# Mini_ELRS_2_4GHz_TX.net
KiCad netlist of a schematic drawn in EAGLE
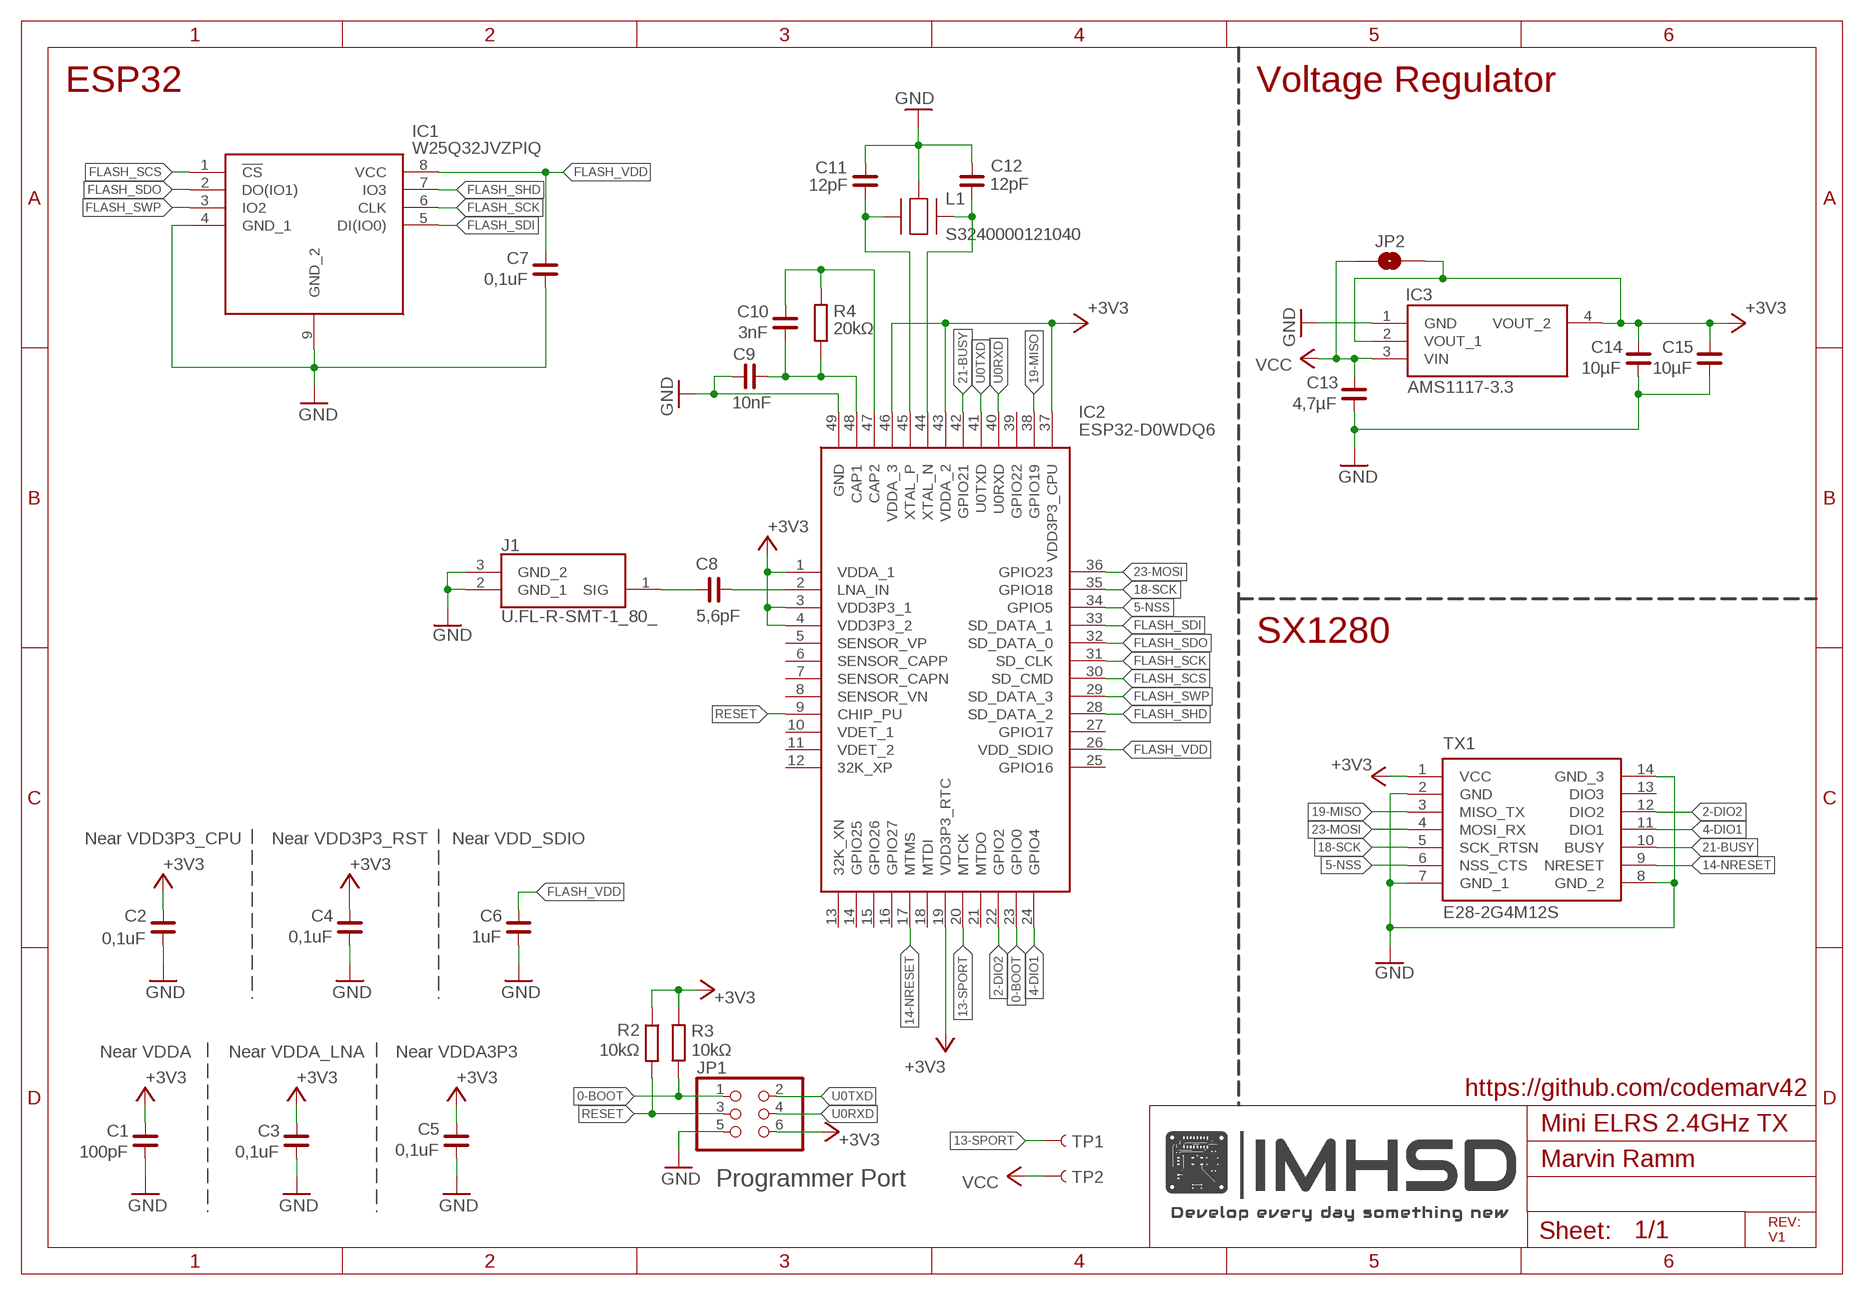
[diagram p0: schematic, sheet 1]

(export (version "E")
  (design (tool "Eeschema 10.0.6"))
  (components
    (comp (ref "C1")
      (value "100pF")
      (footprint "eagle-import:C0402")
      (libsource (lib "eagle-import") (part "C_0402"))
    )
    (comp (ref "C2")
      (value "0,1uF")
      (footprint "eagle-import:C0402")
      (libsource (lib "eagle-import") (part "C_0402"))
    )
    (comp (ref "C3")
      (value "0,1uF")
      (footprint "eagle-import:C0402")
      (libsource (lib "eagle-import") (part "C_0402"))
    )
    (comp (ref "C4")
      (value "0,1uF")
      (footprint "eagle-import:C0402")
      (libsource (lib "eagle-import") (part "C_0402"))
    )
    (comp (ref "C5")
      (value "0,1uF")
      (footprint "eagle-import:C0402")
      (libsource (lib "eagle-import") (part "C_0402"))
    )
    (comp (ref "C6")
      (value "1uF")
      (footprint "eagle-import:C0402")
      (libsource (lib "eagle-import") (part "C_0402"))
    )
    (comp (ref "C7")
      (value "0,1uF")
      (footprint "eagle-import:C0402")
      (libsource (lib "eagle-import") (part "C_0402"))
    )
    (comp (ref "C8")
      (value "5,6pF")
      (footprint "eagle-import:C0402")
      (libsource (lib "eagle-import") (part "C_0402"))
    )
    (comp (ref "C9")
      (value "10nF")
      (footprint "eagle-import:C0402")
      (libsource (lib "eagle-import") (part "C_0402"))
    )
    (comp (ref "C10")
      (value "3nF")
      (footprint "eagle-import:C0402")
      (libsource (lib "eagle-import") (part "C_0402"))
    )
    (comp (ref "C11")
      (value "12pF")
      (footprint "eagle-import:C0402")
      (libsource (lib "eagle-import") (part "C_0402"))
    )
    (comp (ref "C12")
      (value "12pF")
      (footprint "eagle-import:C0402")
      (libsource (lib "eagle-import") (part "C_0402"))
    )
    (comp (ref "C13")
      (value "4,7µF")
      (footprint "eagle-import:C0603")
      (libsource (lib "eagle-import") (part "C_0603"))
    )
    (comp (ref "C14")
      (value "10µF")
      (footprint "eagle-import:C0603")
      (libsource (lib "eagle-import") (part "C_0603"))
    )
    (comp (ref "C15")
      (value "10µF")
      (footprint "eagle-import:C0603")
      (libsource (lib "eagle-import") (part "C_0603"))
    )
    (comp (ref "IC1")
      (value "W25Q128JVPIQ")
      (footprint "eagle-import:SON127P800X600X80-9N")
      (fields (field (name "MOUSER_PART_NUMBER") "454-W25Q128JVPIQ"))
      (libsource (lib "eagle-import") (part "W25Q128JVPIQ"))
    )
    (comp (ref "IC2")
      (value "ESP32-D0WDQ6")
      (footprint "eagle-import:QFN40P600X600X90-49N")
      (fields (field (name "MOUSER_PART_NUMBER") "356-ESP32-D0WDQ6"))
      (libsource (lib "eagle-import") (part "ESP32-D0WDQ6"))
    )
    (comp (ref "IC3")
      (value "AMS1117-3.3")
      (footprint "eagle-import:SOT229P700X180-4N")
      (libsource (lib "eagle-import") (part "AMS1117-3.3"))
    )
    (comp (ref "J1")
      (value "U.FL-R-SMT-1_80_")
      (footprint "eagle-import:UFLRSMT180")
      (fields
        (field (name "MANUFACTURER_PART_NUMBER") "U.FL-R-SMT-1(80)")
        (field (name "MOUSER_PART_NUMBER") "798-UFLRSMT180")
      )
      (libsource (lib "eagle-import") (part "U.FL-R-SMT-1_80_"))
    )
    (comp (ref "JP1")
      (value "ESP32_PRG_PORT")
      (footprint "eagle-import:ESP32_PRG_PORT")
      (libsource (lib "eagle-import") (part "ESP32_PRG_PORT"))
    )
    (comp (ref "JP2")
      (value "JUMPER-SMT_2_NO_SILK")
      (footprint "eagle-import:SMT-JUMPER_2_NO_SILK")
      (libsource (lib "eagle-import") (part "JUMPER-SMT_2_NO_SILK"))
    )
    (comp (ref "L1")
      (value "SMD-3225_4P16MHZ_20PF_10PPM_-4")
      (footprint "eagle-import:SMD3225_4P16MHZ20PF10PPM4085")
      (fields (field (name "MANUFACTURER_PART_NUMBER") "SMD-3225_4P16MHZ 20PF 10PPM -40~+85℃"))
      (libsource (lib "eagle-import") (part "SMD-3225_4P16MHZ_20PF_10PPM_-4"))
    )
    (comp (ref "R2")
      (value "10kΩ")
      (footprint "eagle-import:R0402")
      (libsource (lib "eagle-import") (part "R_0402"))
    )
    (comp (ref "R3")
      (value "10kΩ")
      (footprint "eagle-import:R0402")
      (libsource (lib "eagle-import") (part "R_0402"))
    )
    (comp (ref "R4")
      (value "20kΩ")
      (footprint "eagle-import:R0402")
      (libsource (lib "eagle-import") (part "R_0402"))
    )
    (comp (ref "TP1")
      (value "TEST-POINT3X5")
      (footprint "eagle-import:PAD.03X.05")
      (libsource (lib "eagle-import") (part "TEST-POINT3X5"))
    )
    (comp (ref "TP2")
      (value "TEST-POINT3X5")
      (footprint "eagle-import:PAD.03X.05")
      (libsource (lib "eagle-import") (part "TEST-POINT3X5"))
    )
    (comp (ref "TX1")
      (value "E28-2G4M12S")
      (footprint "eagle-import:E28-2G4M12S")
      (libsource (lib "eagle-import") (part "E28-2G4M12S"))
    )
  )
  (nets
    (net (code "1") (name "+3V3") (class "Default")
      (node (ref "C1") (pin "2") (pinfunction "2_2") (pintype "passive"))
      (node (ref "C14") (pin "1") (pinfunction "1_1") (pintype "passive"))
      (node (ref "C15") (pin "1") (pinfunction "1_1") (pintype "passive"))
      (node (ref "C2") (pin "2") (pinfunction "2_2") (pintype "passive"))
      (node (ref "C3") (pin "2") (pinfunction "2_2") (pintype "passive"))
      (node (ref "C4") (pin "2") (pinfunction "2_2") (pintype "passive"))
      (node (ref "C5") (pin "2") (pinfunction "2_2") (pintype "passive"))
      (node (ref "IC2") (pin "1") (pinfunction "VDDA_1_1") (pintype "bidirectional"))
      (node (ref "IC2") (pin "19") (pinfunction "VDD3P3_RTC_19") (pintype "bidirectional"))
      (node (ref "IC2") (pin "3") (pinfunction "VDD3P3_1_3") (pintype "bidirectional"))
      (node (ref "IC2") (pin "37") (pinfunction "VDD3P3_CPU_37") (pintype "bidirectional"))
      (node (ref "IC2") (pin "4") (pinfunction "VDD3P3_2_4") (pintype "bidirectional"))
      (node (ref "IC2") (pin "43") (pinfunction "VDDA_2_43") (pintype "bidirectional"))
      (node (ref "IC2") (pin "46") (pinfunction "VDDA_3_46") (pintype "bidirectional"))
      (node (ref "IC3") (pin "2") (pinfunction "VOUT_1_2") (pintype "bidirectional"))
      (node (ref "IC3") (pin "4") (pinfunction "VOUT_2_4") (pintype "bidirectional"))
      (node (ref "JP1") (pin "6") (pinfunction "6_6") (pintype "passive"))
      (node (ref "JP2") (pin "2") (pinfunction "2_2") (pintype "passive"))
      (node (ref "R2") (pin "2") (pinfunction "2_2") (pintype "passive"))
      (node (ref "R3") (pin "1") (pinfunction "1_1") (pintype "passive"))
      (node (ref "TX1") (pin "1") (pinfunction "VCC_1") (pintype "bidirectional"))
    )
    (net (code "2") (name "0-BOOT") (class "Default")
      (node (ref "IC2") (pin "23") (pinfunction "GPIO0_23") (pintype "bidirectional"))
      (node (ref "JP1") (pin "1") (pinfunction "1_1") (pintype "passive"))
      (node (ref "R3") (pin "2") (pinfunction "2_2") (pintype "passive"))
    )
    (net (code "3") (name "2-DIO2") (class "Default")
      (node (ref "IC2") (pin "22") (pinfunction "GPIO2_22") (pintype "bidirectional"))
      (node (ref "TX1") (pin "12") (pinfunction "DIO2_12") (pintype "bidirectional"))
    )
    (net (code "4") (name "4-DIO1") (class "Default")
      (node (ref "IC2") (pin "24") (pinfunction "GPIO4_24") (pintype "bidirectional"))
      (node (ref "TX1") (pin "11") (pinfunction "DIO1_11") (pintype "bidirectional"))
    )
    (net (code "5") (name "5-NSS") (class "Default")
      (node (ref "IC2") (pin "34") (pinfunction "GPIO5_34") (pintype "bidirectional"))
      (node (ref "TX1") (pin "6") (pinfunction "NSS_CTS_6") (pintype "bidirectional"))
    )
    (net (code "6") (name "13-SPORT") (class "Default")
      (node (ref "IC2") (pin "20") (pinfunction "MTCK_20") (pintype "bidirectional"))
      (node (ref "TP1") (pin "1") (pinfunction "1_1") (pintype "bidirectional"))
    )
    (net (code "7") (name "14-NRESET") (class "Default")
      (node (ref "IC2") (pin "17") (pinfunction "MTMS_17") (pintype "bidirectional"))
      (node (ref "TX1") (pin "9") (pinfunction "NRESET_9") (pintype "bidirectional"))
    )
    (net (code "8") (name "18-SCK") (class "Default")
      (node (ref "IC2") (pin "35") (pinfunction "GPIO18_35") (pintype "bidirectional"))
      (node (ref "TX1") (pin "5") (pinfunction "SCK_RTSN_5") (pintype "bidirectional"))
    )
    (net (code "9") (name "19-MISO") (class "Default")
      (node (ref "IC2") (pin "38") (pinfunction "GPIO19_38") (pintype "bidirectional"))
      (node (ref "TX1") (pin "3") (pinfunction "MISO_TX_3") (pintype "bidirectional"))
    )
    (net (code "10") (name "21-BUSY") (class "Default")
      (node (ref "IC2") (pin "42") (pinfunction "GPIO21_42") (pintype "bidirectional"))
      (node (ref "TX1") (pin "10") (pinfunction "BUSY_10") (pintype "bidirectional"))
    )
    (net (code "11") (name "23-MOSI") (class "Default")
      (node (ref "IC2") (pin "36") (pinfunction "GPIO23_36") (pintype "bidirectional"))
      (node (ref "TX1") (pin "4") (pinfunction "MOSI_RX_4") (pintype "bidirectional"))
    )
    (net (code "12") (name "FLASH_SCK") (class "Default")
      (node (ref "IC1") (pin "6") (pinfunction "CLK_6") (pintype "bidirectional"))
      (node (ref "IC2") (pin "31") (pinfunction "SD_CLK_31") (pintype "bidirectional"))
    )
    (net (code "13") (name "FLASH_SCS") (class "Default")
      (node (ref "IC1") (pin "1") (pinfunction "~{CS}_1") (pintype "bidirectional"))
      (node (ref "IC2") (pin "30") (pinfunction "SD_CMD_30") (pintype "bidirectional"))
    )
    (net (code "14") (name "FLASH_SDI") (class "Default")
      (node (ref "IC1") (pin "5") (pinfunction "DI(IO0)_5") (pintype "bidirectional"))
      (node (ref "IC2") (pin "33") (pinfunction "SD_DATA_1_33") (pintype "bidirectional"))
    )
    (net (code "15") (name "FLASH_SDO") (class "Default")
      (node (ref "IC1") (pin "2") (pinfunction "DO(IO1)_2") (pintype "bidirectional"))
      (node (ref "IC2") (pin "32") (pinfunction "SD_DATA_0_32") (pintype "bidirectional"))
    )
    (net (code "16") (name "FLASH_SHD") (class "Default")
      (node (ref "IC1") (pin "7") (pinfunction "IO3_7") (pintype "bidirectional"))
      (node (ref "IC2") (pin "28") (pinfunction "SD_DATA_2_28") (pintype "bidirectional"))
    )
    (net (code "17") (name "FLASH_SWP") (class "Default")
      (node (ref "IC1") (pin "3") (pinfunction "IO2_3") (pintype "bidirectional"))
      (node (ref "IC2") (pin "29") (pinfunction "SD_DATA_3_29") (pintype "bidirectional"))
    )
    (net (code "18") (name "FLASH_VDD") (class "Default")
      (node (ref "C6") (pin "2") (pinfunction "2_2") (pintype "passive"))
      (node (ref "C7") (pin "2") (pinfunction "2_2") (pintype "passive"))
      (node (ref "IC1") (pin "8") (pinfunction "VCC_8") (pintype "bidirectional"))
      (node (ref "IC2") (pin "26") (pinfunction "VDD_SDIO_26") (pintype "bidirectional"))
    )
    (net (code "19") (name "GND") (class "Default")
      (node (ref "C1") (pin "1") (pinfunction "1_1") (pintype "passive"))
      (node (ref "C11") (pin "1") (pinfunction "1_1") (pintype "passive"))
      (node (ref "C12") (pin "1") (pinfunction "1_1") (pintype "passive"))
      (node (ref "C13") (pin "2") (pinfunction "2_2") (pintype "passive"))
      (node (ref "C14") (pin "2") (pinfunction "2_2") (pintype "passive"))
      (node (ref "C15") (pin "2") (pinfunction "2_2") (pintype "passive"))
      (node (ref "C2") (pin "1") (pinfunction "1_1") (pintype "passive"))
      (node (ref "C3") (pin "1") (pinfunction "1_1") (pintype "passive"))
      (node (ref "C4") (pin "1") (pinfunction "1_1") (pintype "passive"))
      (node (ref "C5") (pin "1") (pinfunction "1_1") (pintype "passive"))
      (node (ref "C6") (pin "1") (pinfunction "1_1") (pintype "passive"))
      (node (ref "C7") (pin "1") (pinfunction "1_1") (pintype "passive"))
      (node (ref "C9") (pin "1") (pinfunction "1_1") (pintype "passive"))
      (node (ref "IC1") (pin "4") (pinfunction "GND_1_4") (pintype "bidirectional"))
      (node (ref "IC1") (pin "9") (pinfunction "GND_2_9") (pintype "bidirectional"))
      (node (ref "IC2") (pin "49") (pinfunction "GND_49") (pintype "bidirectional"))
      (node (ref "IC3") (pin "1") (pinfunction "GND_1") (pintype "bidirectional"))
      (node (ref "J1") (pin "2") (pinfunction "GND_1_2") (pintype "bidirectional"))
      (node (ref "J1") (pin "3") (pinfunction "GND_2_3") (pintype "bidirectional"))
      (node (ref "JP1") (pin "5") (pinfunction "5_5") (pintype "passive"))
      (node (ref "L1") (pin "2") (pinfunction "GND_2_2") (pintype "bidirectional"))
      (node (ref "L1") (pin "4") (pinfunction "GND_2_4") (pintype "bidirectional"))
      (node (ref "TX1") (pin "14") (pinfunction "GND_3_14") (pintype "bidirectional"))
      (node (ref "TX1") (pin "2") (pinfunction "GND_2") (pintype "bidirectional"))
      (node (ref "TX1") (pin "7") (pinfunction "GND_1_7") (pintype "bidirectional"))
      (node (ref "TX1") (pin "8") (pinfunction "GND_2_8") (pintype "bidirectional"))
    )
    (net (code "20") (name "Net-(IC2-CAP1)") (class "Default")
      (node (ref "C10") (pin "1") (pinfunction "1_1") (pintype "passive"))
      (node (ref "C9") (pin "2") (pinfunction "2_2") (pintype "passive"))
      (node (ref "IC2") (pin "48") (pinfunction "CAP1_48") (pintype "bidirectional"))
      (node (ref "R4") (pin "2") (pinfunction "2_2") (pintype "passive"))
    )
    (net (code "21") (name "Net-(IC2-CAP2)") (class "Default")
      (node (ref "C10") (pin "2") (pinfunction "2_2") (pintype "passive"))
      (node (ref "IC2") (pin "47") (pinfunction "CAP2_47") (pintype "bidirectional"))
      (node (ref "R4") (pin "1") (pinfunction "1_1") (pintype "passive"))
    )
    (net (code "22") (name "Net-(IC2-LNA_IN)") (class "Default")
      (node (ref "C8") (pin "1") (pinfunction "1_1") (pintype "passive"))
      (node (ref "IC2") (pin "2") (pinfunction "LNA_IN_2") (pintype "bidirectional"))
    )
    (net (code "23") (name "Net-(IC2-XTAL_N)") (class "Default")
      (node (ref "C12") (pin "2") (pinfunction "2_2") (pintype "passive"))
      (node (ref "IC2") (pin "44") (pinfunction "XTAL_N_44") (pintype "bidirectional"))
      (node (ref "L1") (pin "3") (pinfunction "CRYSTAL_2_3") (pintype "bidirectional"))
    )
    (net (code "24") (name "Net-(IC2-XTAL_P)") (class "Default")
      (node (ref "C11") (pin "2") (pinfunction "2_2") (pintype "passive"))
      (node (ref "IC2") (pin "45") (pinfunction "XTAL_P_45") (pintype "bidirectional"))
      (node (ref "L1") (pin "1") (pinfunction "CRYSTAL_1_1") (pintype "bidirectional"))
    )
    (net (code "25") (name "Net-(J1-SIG)") (class "Default")
      (node (ref "C8") (pin "2") (pinfunction "2_2") (pintype "passive"))
      (node (ref "J1") (pin "1") (pinfunction "SIG_1") (pintype "bidirectional"))
    )
    (net (code "26") (name "RESET") (class "Default")
      (node (ref "IC2") (pin "9") (pinfunction "CHIP_PU_9") (pintype "bidirectional"))
      (node (ref "JP1") (pin "3") (pinfunction "3_3") (pintype "passive"))
      (node (ref "R2") (pin "1") (pinfunction "1_1") (pintype "passive"))
    )
    (net (code "27") (name "U0RXD") (class "Default")
      (node (ref "IC2") (pin "40") (pinfunction "U0RXD_40") (pintype "bidirectional"))
      (node (ref "JP1") (pin "4") (pinfunction "4_4") (pintype "passive"))
    )
    (net (code "28") (name "U0TXD") (class "Default")
      (node (ref "IC2") (pin "41") (pinfunction "U0TXD_41") (pintype "bidirectional"))
      (node (ref "JP1") (pin "2") (pinfunction "2_2") (pintype "passive"))
    )
    (net (code "29") (name "VCC") (class "Default")
      (node (ref "C13") (pin "1") (pinfunction "1_1") (pintype "passive"))
      (node (ref "IC3") (pin "3") (pinfunction "VIN_3") (pintype "bidirectional"))
      (node (ref "JP2") (pin "1") (pinfunction "1_1") (pintype "passive"))
      (node (ref "TP2") (pin "1") (pinfunction "1_1") (pintype "bidirectional"))
    )
    (net (code "30") (name "unconnected-(IC2-32K_XN-Pad13)") (class "Default")
      (node (ref "IC2") (pin "13") (pinfunction "32K_XN_13") (pintype "bidirectional"))
    )
    (net (code "31") (name "unconnected-(IC2-32K_XP-Pad12)") (class "Default")
      (node (ref "IC2") (pin "12") (pinfunction "32K_XP_12") (pintype "bidirectional"))
    )
    (net (code "32") (name "unconnected-(IC2-GPIO16-Pad25)") (class "Default")
      (node (ref "IC2") (pin "25") (pinfunction "GPIO16_25") (pintype "bidirectional"))
    )
    (net (code "33") (name "unconnected-(IC2-GPIO17-Pad27)") (class "Default")
      (node (ref "IC2") (pin "27") (pinfunction "GPIO17_27") (pintype "bidirectional"))
    )
    (net (code "34") (name "unconnected-(IC2-GPIO22-Pad39)") (class "Default")
      (node (ref "IC2") (pin "39") (pinfunction "GPIO22_39") (pintype "bidirectional"))
    )
    (net (code "35") (name "unconnected-(IC2-GPIO25-Pad14)") (class "Default")
      (node (ref "IC2") (pin "14") (pinfunction "GPIO25_14") (pintype "bidirectional"))
    )
    (net (code "36") (name "unconnected-(IC2-GPIO26-Pad15)") (class "Default")
      (node (ref "IC2") (pin "15") (pinfunction "GPIO26_15") (pintype "bidirectional"))
    )
    (net (code "37") (name "unconnected-(IC2-GPIO27-Pad16)") (class "Default")
      (node (ref "IC2") (pin "16") (pinfunction "GPIO27_16") (pintype "bidirectional"))
    )
    (net (code "38") (name "unconnected-(IC2-MTDI-Pad18)") (class "Default")
      (node (ref "IC2") (pin "18") (pinfunction "MTDI_18") (pintype "bidirectional"))
    )
    (net (code "39") (name "unconnected-(IC2-MTDO-Pad21)") (class "Default")
      (node (ref "IC2") (pin "21") (pinfunction "MTDO_21") (pintype "bidirectional"))
    )
    (net (code "40") (name "unconnected-(IC2-SENSOR_CAPN-Pad7)") (class "Default")
      (node (ref "IC2") (pin "7") (pinfunction "SENSOR_CAPN_7") (pintype "bidirectional"))
    )
    (net (code "41") (name "unconnected-(IC2-SENSOR_CAPP-Pad6)") (class "Default")
      (node (ref "IC2") (pin "6") (pinfunction "SENSOR_CAPP_6") (pintype "bidirectional"))
    )
    (net (code "42") (name "unconnected-(IC2-SENSOR_VN-Pad8)") (class "Default")
      (node (ref "IC2") (pin "8") (pinfunction "SENSOR_VN_8") (pintype "bidirectional"))
    )
    (net (code "43") (name "unconnected-(IC2-SENSOR_VP-Pad5)") (class "Default")
      (node (ref "IC2") (pin "5") (pinfunction "SENSOR_VP_5") (pintype "bidirectional"))
    )
    (net (code "44") (name "unconnected-(IC2-VDET_1-Pad10)") (class "Default")
      (node (ref "IC2") (pin "10") (pinfunction "VDET_1_10") (pintype "bidirectional"))
    )
    (net (code "45") (name "unconnected-(IC2-VDET_2-Pad11)") (class "Default")
      (node (ref "IC2") (pin "11") (pinfunction "VDET_2_11") (pintype "bidirectional"))
    )
    (net (code "46") (name "unconnected-(TX1-DIO3-Pad13)") (class "Default")
      (node (ref "TX1") (pin "13") (pinfunction "DIO3_13") (pintype "bidirectional"))
    )
  )
)
